# SCH_Mach_DK_Relay_3_Kenh.net
KiCad netlist of a schematic drawn in Altium Designer
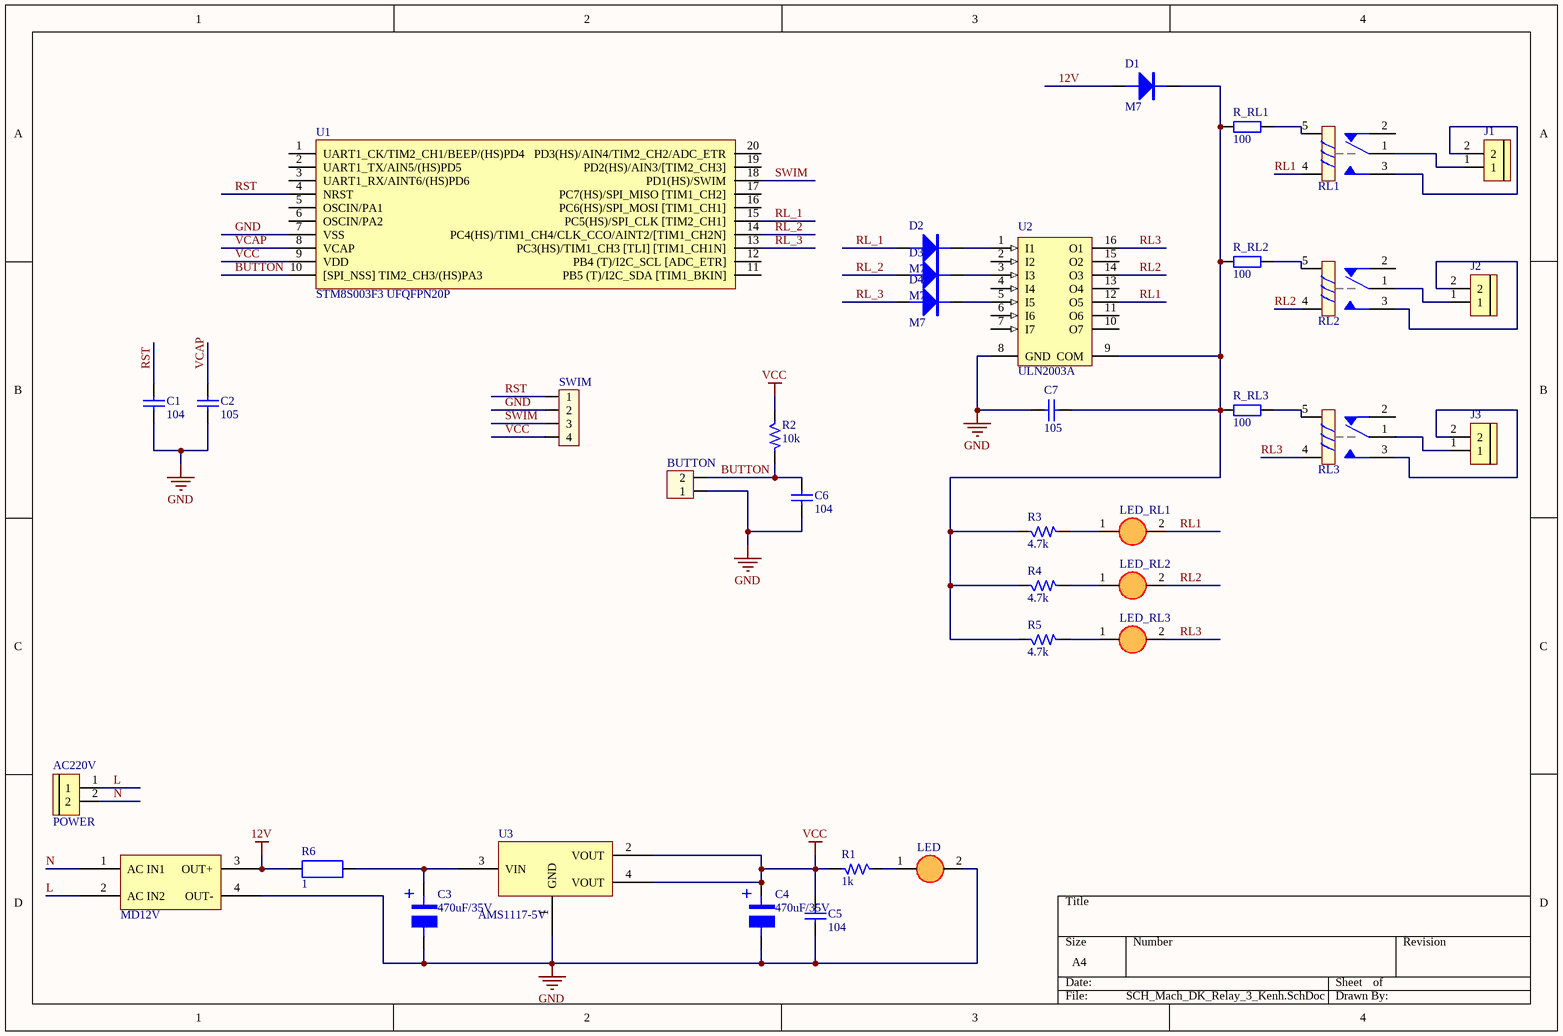
[diagram p0: SCH_Mach_DK_Relay_3_Kenh.SchDoc]

(export (version "E")
  (design (tool "Eeschema 10.0.6"))
  (components
    (comp (ref "AC220V")
      (value "POWER")
      (footprint "BIG_Header 2")
      (description "Big Header 2")
      (libsource (lib "") (part "Header 2_1"))
    )
    (comp (ref "BUTTON")
      (value "Header 2")
      (footprint "Header 2 Duc Cong 2.54")
      (description "Header 2 (Green)")
      (libsource (lib "MH_THU VIEN CHUAN 12-03-2015") (part "Hed2"))
    )
    (comp (ref "C1")
      (value "104")
      (footprint "Tu 0805")
      (libsource (lib "MH_THU VIEN CHUAN 12-03-2015") (part "CAP 0805"))
    )
    (comp (ref "C2")
      (value "105")
      (footprint "Tu 0805")
      (libsource (lib "MH_THU VIEN CHUAN 12-03-2015") (part "CAP 0805"))
    )
    (comp (ref "C3")
      (value "470uF/35V")
      (footprint "MH_THU VIEN CHUAN 13-03-2015 :Tu Hoa 450uF - 16V")
      (libsource (lib "MH_THU VIEN CHUAN 12-03-2015") (part "Cap100uF 50V"))
    )
    (comp (ref "C4")
      (value "470uF/35V")
      (footprint "MH_THU VIEN CHUAN 13-03-2015 :Tu Hoa 450uF - 16V")
      (libsource (lib "MH_THU VIEN CHUAN 12-03-2015") (part "Cap100uF 50V"))
    )
    (comp (ref "C5")
      (value "104")
      (footprint "Tu 0805")
      (libsource (lib "MH_THU VIEN CHUAN 12-03-2015") (part "CAP 0805"))
    )
    (comp (ref "C6")
      (value "104")
      (footprint "Tu 0805")
      (libsource (lib "MH_THU VIEN CHUAN 12-03-2015") (part "CAP 0805"))
    )
    (comp (ref "C7")
      (value "105")
      (footprint "Tu 0805")
      (libsource (lib "MH_THU VIEN CHUAN 12-03-2015") (part "CAP 0805"))
    )
    (comp (ref "D1")
      (value "M7")
      (footprint "SMB")
      (description "Diode")
      (libsource (lib "MH_THU VIEN CHUAN 12-03-2015") (part "DIODE"))
    )
    (comp (ref "D2")
      (value "M7")
      (footprint "SMB")
      (description "Diode")
      (libsource (lib "MH_THU VIEN CHUAN 12-03-2015") (part "DIODE"))
    )
    (comp (ref "D3")
      (value "M7")
      (footprint "SMB")
      (description "Diode")
      (libsource (lib "MH_THU VIEN CHUAN 12-03-2015") (part "DIODE"))
    )
    (comp (ref "D4")
      (value "M7")
      (footprint "SMB")
      (description "Diode")
      (libsource (lib "MH_THU VIEN CHUAN 12-03-2015") (part "DIODE"))
    )
    (comp (ref "J1")
      (value "Header 2")
      (footprint "BIG_Header 2")
      (description "Big Header 2")
      (libsource (lib "MH_THU VIEN CHUAN 12-03-2015") (part "Header 2"))
    )
    (comp (ref "J2")
      (value "Header 2")
      (footprint "BIG_Header 2")
      (description "Big Header 2")
      (libsource (lib "MH_THU VIEN CHUAN 12-03-2015") (part "Header 2"))
    )
    (comp (ref "J3")
      (value "Header 2")
      (footprint "BIG_Header 2")
      (description "Big Header 2")
      (libsource (lib "MH_THU VIEN CHUAN 12-03-2015") (part "Header 2"))
    )
    (comp (ref "LED")
      (value "LED3")
      (footprint "LED RED 5mm")
      (description "LED 3mm")
      (libsource (lib "MH_THU VIEN CHUAN 12-03-2015") (part "LED 3mm"))
    )
    (comp (ref "LED_RL1")
      (value "LED3")
      (footprint "LED RED 5mm")
      (description "LED 3mm")
      (libsource (lib "MH_THU VIEN CHUAN 12-03-2015") (part "LED 3mm"))
    )
    (comp (ref "LED_RL2")
      (value "LED3")
      (footprint "LED RED 5mm")
      (description "LED 3mm")
      (libsource (lib "MH_THU VIEN CHUAN 12-03-2015") (part "LED 3mm"))
    )
    (comp (ref "LED_RL3")
      (value "LED3")
      (footprint "LED RED 5mm")
      (description "LED 3mm")
      (libsource (lib "MH_THU VIEN CHUAN 12-03-2015") (part "LED 3mm"))
    )
    (comp (ref "MD12V")
      (value "Module Driver LED 1x3W")
      (footprint "Module Driver LED")
      (libsource (lib "MH_THU VIEN CHUAN 12-03-2015") (part "Module DK LED 1X3w"))
    )
    (comp (ref "R1")
      (value "1k")
      (footprint "Tro SMD 0805")
      (description "Resistor 1/4W")
      (libsource (lib "MH_THU VIEN CHUAN 12-03-2015") (part "Res"))
    )
    (comp (ref "R2")
      (value "10k")
      (footprint "Tro SMD 0805")
      (description "Resistor 1/4W")
      (libsource (lib "MH_THU VIEN CHUAN 12-03-2015") (part "Res"))
    )
    (comp (ref "R3")
      (value "4.7k")
      (footprint "Tro SMD 0805")
      (description "Resistor 1/4W")
      (libsource (lib "MH_THU VIEN CHUAN 12-03-2015") (part "Res"))
    )
    (comp (ref "R4")
      (value "4.7k")
      (footprint "Tro SMD 0805")
      (description "Resistor 1/4W")
      (libsource (lib "MH_THU VIEN CHUAN 12-03-2015") (part "Res"))
    )
    (comp (ref "R5")
      (value "4.7k")
      (footprint "Tro SMD 0805")
      (description "Resistor 1/4W")
      (libsource (lib "MH_THU VIEN CHUAN 12-03-2015") (part "Res"))
    )
    (comp (ref "R6")
      (value "1")
      (footprint "R2W")
      (description "Resistor 2W")
      (libsource (lib "MH_THU VIEN CHUAN 12-03-2015") (part "R2W"))
    )
    (comp (ref "RL1")
      (value "Relay ?V - 10A")
      (footprint "RELAY5PIN-10A")
      (description "Relay SPDT,10A - 12VDC 5 Pin")
      (libsource (lib "MH_THU VIEN CHUAN 12-03-2015") (part "Relay 10A"))
    )
    (comp (ref "RL2")
      (value "Relay ?V - 10A")
      (footprint "RELAY5PIN-10A")
      (description "Relay SPDT,10A - 12VDC 5 Pin")
      (libsource (lib "MH_THU VIEN CHUAN 12-03-2015") (part "Relay 10A"))
    )
    (comp (ref "RL3")
      (value "Relay ?V - 10A")
      (footprint "RELAY5PIN-10A")
      (description "Relay SPDT,10A - 12VDC 5 Pin")
      (libsource (lib "MH_THU VIEN CHUAN 12-03-2015") (part "Relay 10A"))
    )
    (comp (ref "R_RL1")
      (value "100")
      (footprint "1206 SMD")
      (description "Resistor 1/4W")
      (libsource (lib "MH_THU VIEN CHUAN 12-03-2015") (part "R1/4W"))
    )
    (comp (ref "R_RL2")
      (value "100")
      (footprint "1206 SMD")
      (description "Resistor 1/4W")
      (libsource (lib "MH_THU VIEN CHUAN 12-03-2015") (part "R1/4W"))
    )
    (comp (ref "R_RL3")
      (value "100")
      (footprint "1206 SMD")
      (description "Resistor 1/4W")
      (libsource (lib "MH_THU VIEN CHUAN 12-03-2015") (part "R1/4W"))
    )
    (comp (ref "SWIM")
      (value "JP4")
      (footprint "JP4")
      (libsource (lib "MH_THU VIEN CHUAN 12-03-2015") (part "JP4"))
    )
    (comp (ref "U1")
      (value "STM8S003F3 UFQFPN20P")
      (footprint "TSSOP20")
      (libsource (lib "MH_THU VIEN CHUAN 12-03-2015") (part "STM8S003F3 UFQFPN20P"))
    )
    (comp (ref "U2")
      (value "ULN2003A")
      (footprint "SOP16")
      (description "High-Voltage, High-Current Darlington Array")
      (fields (field (name "PUBLISHER") "Altium Limited"))
      (libsource (lib "MH_THU VIEN CHUAN 12-03-2015") (part "ULN2003A"))
    )
    (comp (ref "U3")
      (value "AMS1117-5V")
      (footprint "SOT223-4N")
      (description "AMS")
      (libsource (lib "MH_THU VIEN CHUAN 12-03-2015") (part "AMS1117"))
    )
  )
  (nets
    (net (code "1") (name "/BUTTON") (class "Default")
      (node (ref "BUTTON") (pin "2") (pinfunction "2_2") (pintype "passive"))
      (node (ref "C6") (pin "2") (pinfunction "2_2") (pintype "passive"))
      (node (ref "R2") (pin "2") (pinfunction "2_2") (pintype "passive"))
      (node (ref "U1") (pin "10") (pinfunction "[SPI_NSS]_TIM2_CH3/(HS)PA3_10") (pintype "passive"))
    )
    (net (code "2") (name "/L") (class "Default")
      (node (ref "AC220V") (pin "1") (pinfunction "1_1") (pintype "passive"))
      (node (ref "MD12V") (pin "2") (pinfunction "AC_IN2_2") (pintype "passive"))
    )
    (net (code "3") (name "/N") (class "Default")
      (node (ref "AC220V") (pin "2") (pinfunction "2_2") (pintype "passive"))
      (node (ref "MD12V") (pin "1") (pinfunction "AC_IN1_1") (pintype "passive"))
    )
    (net (code "4") (name "/RL1") (class "Default")
      (node (ref "LED_RL1") (pin "2") (pinfunction "K_2") (pintype "passive"))
      (node (ref "RL1") (pin "4") (pinfunction "4_4") (pintype "passive"))
      (node (ref "U2") (pin "12") (pinfunction "O5_12") (pintype "open_collector"))
    )
    (net (code "5") (name "/RL2") (class "Default")
      (node (ref "LED_RL2") (pin "2") (pinfunction "K_2") (pintype "passive"))
      (node (ref "RL2") (pin "4") (pinfunction "4_4") (pintype "passive"))
      (node (ref "U2") (pin "14") (pinfunction "O3_14") (pintype "open_collector"))
    )
    (net (code "6") (name "/RL3") (class "Default")
      (node (ref "LED_RL3") (pin "2") (pinfunction "K_2") (pintype "passive"))
      (node (ref "RL3") (pin "4") (pinfunction "4_4") (pintype "passive"))
      (node (ref "U2") (pin "16") (pinfunction "O1_16") (pintype "open_collector"))
    )
    (net (code "7") (name "/RL_1") (class "Default")
      (node (ref "D2") (pin "1") (pinfunction "1_1") (pintype "passive"))
      (node (ref "U1") (pin "15") (pinfunction "PC5(HS)/SPI_CLK_[TIM2_CH1]_15") (pintype "passive"))
    )
    (net (code "8") (name "/RL_2") (class "Default")
      (node (ref "D3") (pin "1") (pinfunction "1_1") (pintype "passive"))
      (node (ref "U1") (pin "14") (pinfunction "PC4(HS)/TIM1_CH4/CLK_CCO/AINT2/[TIM1_CH2N]_14") (pintype "passive"))
    )
    (net (code "9") (name "/RL_3") (class "Default")
      (node (ref "D4") (pin "1") (pinfunction "1_1") (pintype "passive"))
      (node (ref "U1") (pin "13") (pinfunction "PC3(HS)/TIM1_CH3_[TLI]_[TIM1_CH1N]_13") (pintype "passive"))
    )
    (net (code "10") (name "/RST") (class "Default")
      (node (ref "C1") (pin "2") (pinfunction "2_2") (pintype "passive"))
      (node (ref "SWIM") (pin "1") (pinfunction "1_1") (pintype "passive"))
      (node (ref "U1") (pin "4") (pinfunction "NRST_4") (pintype "passive"))
    )
    (net (code "11") (name "/SWIM") (class "Default")
      (node (ref "SWIM") (pin "3") (pinfunction "3_3") (pintype "passive"))
      (node (ref "U1") (pin "18") (pinfunction "PD1(HS)/SWIM_18") (pintype "passive"))
    )
    (net (code "12") (name "/VCAP") (class "Default")
      (node (ref "C2") (pin "2") (pinfunction "2_2") (pintype "passive"))
      (node (ref "U1") (pin "8") (pinfunction "VCAP_8") (pintype "passive"))
    )
    (net (code "13") (name "12V") (class "Default")
      (node (ref "D1") (pin "1") (pinfunction "1_1") (pintype "passive"))
      (node (ref "MD12V") (pin "3") (pinfunction "OUT+_3") (pintype "passive"))
      (node (ref "R6") (pin "1") (pinfunction "1_1") (pintype "passive"))
    )
    (net (code "14") (name "GND") (class "Default")
      (node (ref "BUTTON") (pin "1") (pinfunction "1_1") (pintype "passive"))
      (node (ref "C1") (pin "1") (pinfunction "1_1") (pintype "passive"))
      (node (ref "C2") (pin "1") (pinfunction "1_1") (pintype "passive"))
      (node (ref "C3") (pin "2") (pinfunction "2_2") (pintype "passive"))
      (node (ref "C4") (pin "2") (pinfunction "2_2") (pintype "passive"))
      (node (ref "C5") (pin "1") (pinfunction "1_1") (pintype "passive"))
      (node (ref "C6") (pin "1") (pinfunction "1_1") (pintype "passive"))
      (node (ref "C7") (pin "2") (pinfunction "2_2") (pintype "passive"))
      (node (ref "LED") (pin "2") (pinfunction "K_2") (pintype "passive"))
      (node (ref "MD12V") (pin "4") (pinfunction "OUT-_4") (pintype "passive"))
      (node (ref "SWIM") (pin "2") (pinfunction "2_2") (pintype "passive"))
      (node (ref "U1") (pin "7") (pinfunction "VSS_7") (pintype "passive"))
      (node (ref "U2") (pin "8") (pinfunction "GND_8") (pintype "power_in"))
      (node (ref "U3") (pin "1") (pinfunction "GND_1") (pintype "passive"))
    )
    (net (code "15") (name "Net-(J1-Pad1)") (class "Default")
      (node (ref "J1") (pin "1") (pinfunction "1_1") (pintype "passive"))
      (node (ref "RL1") (pin "1") (pinfunction "1_1") (pintype "passive"))
    )
    (net (code "16") (name "Net-(J1-Pad2)") (class "Default")
      (node (ref "J1") (pin "2") (pinfunction "2_2") (pintype "passive"))
      (node (ref "RL1") (pin "3") (pinfunction "3_3") (pintype "passive"))
    )
    (net (code "17") (name "Net-(J2-Pad1)") (class "Default")
      (node (ref "J2") (pin "1") (pinfunction "1_1") (pintype "passive"))
      (node (ref "RL2") (pin "1") (pinfunction "1_1") (pintype "passive"))
    )
    (net (code "18") (name "Net-(J2-Pad2)") (class "Default")
      (node (ref "J2") (pin "2") (pinfunction "2_2") (pintype "passive"))
      (node (ref "RL2") (pin "3") (pinfunction "3_3") (pintype "passive"))
    )
    (net (code "19") (name "Net-(J3-Pad1)") (class "Default")
      (node (ref "J3") (pin "1") (pinfunction "1_1") (pintype "passive"))
      (node (ref "RL3") (pin "1") (pinfunction "1_1") (pintype "passive"))
    )
    (net (code "20") (name "Net-(J3-Pad2)") (class "Default")
      (node (ref "J3") (pin "2") (pinfunction "2_2") (pintype "passive"))
      (node (ref "RL3") (pin "3") (pinfunction "3_3") (pintype "passive"))
    )
    (net (code "21") (name "Net-(LED-A)") (class "Default")
      (node (ref "LED") (pin "1") (pinfunction "A_1") (pintype "passive"))
      (node (ref "R1") (pin "1") (pinfunction "1_1") (pintype "passive"))
    )
    (net (code "22") (name "Net-(LED_RL1-A)") (class "Default")
      (node (ref "LED_RL1") (pin "1") (pinfunction "A_1") (pintype "passive"))
      (node (ref "R3") (pin "2") (pinfunction "2_2") (pintype "passive"))
    )
    (net (code "23") (name "Net-(LED_RL2-A)") (class "Default")
      (node (ref "LED_RL2") (pin "1") (pinfunction "A_1") (pintype "passive"))
      (node (ref "R4") (pin "2") (pinfunction "2_2") (pintype "passive"))
    )
    (net (code "24") (name "Net-(LED_RL3-A)") (class "Default")
      (node (ref "LED_RL3") (pin "1") (pinfunction "A_1") (pintype "passive"))
      (node (ref "R5") (pin "2") (pinfunction "2_2") (pintype "passive"))
    )
    (net (code "25") (name "Net-(RL1-Pad5)") (class "Default")
      (node (ref "RL1") (pin "5") (pinfunction "5_5") (pintype "passive"))
      (node (ref "R_RL1") (pin "2") (pinfunction "2_2") (pintype "passive"))
    )
    (net (code "26") (name "Net-(RL2-Pad5)") (class "Default")
      (node (ref "RL2") (pin "5") (pinfunction "5_5") (pintype "passive"))
      (node (ref "R_RL2") (pin "2") (pinfunction "2_2") (pintype "passive"))
    )
    (net (code "27") (name "Net-(RL3-Pad5)") (class "Default")
      (node (ref "RL3") (pin "5") (pinfunction "5_5") (pintype "passive"))
      (node (ref "R_RL3") (pin "2") (pinfunction "2_2") (pintype "passive"))
    )
    (net (code "28") (name "Net-(U2-COM)") (class "Default")
      (node (ref "C7") (pin "1") (pinfunction "1_1") (pintype "passive"))
      (node (ref "D1") (pin "2") (pinfunction "2_2") (pintype "passive"))
      (node (ref "R3") (pin "1") (pinfunction "1_1") (pintype "passive"))
      (node (ref "R4") (pin "1") (pinfunction "1_1") (pintype "passive"))
      (node (ref "R5") (pin "1") (pinfunction "1_1") (pintype "passive"))
      (node (ref "R_RL1") (pin "1") (pinfunction "1_1") (pintype "passive"))
      (node (ref "R_RL2") (pin "1") (pinfunction "1_1") (pintype "passive"))
      (node (ref "R_RL3") (pin "1") (pinfunction "1_1") (pintype "passive"))
      (node (ref "U2") (pin "9") (pinfunction "COM_9") (pintype "passive"))
    )
    (net (code "29") (name "Net-(U2-I1)") (class "Default")
      (node (ref "D2") (pin "2") (pinfunction "2_2") (pintype "passive"))
      (node (ref "U2") (pin "1") (pinfunction "I1_1") (pintype "input"))
    )
    (net (code "30") (name "Net-(U2-I3)") (class "Default")
      (node (ref "D3") (pin "2") (pinfunction "2_2") (pintype "passive"))
      (node (ref "U2") (pin "3") (pinfunction "I3_3") (pintype "input"))
    )
    (net (code "31") (name "Net-(U2-I5)") (class "Default")
      (node (ref "D4") (pin "2") (pinfunction "2_2") (pintype "passive"))
      (node (ref "U2") (pin "5") (pinfunction "I5_5") (pintype "input"))
    )
    (net (code "32") (name "Net-(U3-VIN)") (class "Default")
      (node (ref "C3") (pin "1") (pinfunction "1_1") (pintype "passive"))
      (node (ref "R6") (pin "2") (pinfunction "2_2") (pintype "passive"))
      (node (ref "U3") (pin "3") (pinfunction "VIN_3") (pintype "passive"))
    )
    (net (code "33") (name "VCC") (class "Default")
      (node (ref "C4") (pin "1") (pinfunction "1_1") (pintype "passive"))
      (node (ref "C5") (pin "2") (pinfunction "2_2") (pintype "passive"))
      (node (ref "R1") (pin "2") (pinfunction "2_2") (pintype "passive"))
      (node (ref "R2") (pin "1") (pinfunction "1_1") (pintype "passive"))
      (node (ref "SWIM") (pin "4") (pinfunction "4_4") (pintype "passive"))
      (node (ref "U1") (pin "9") (pinfunction "VDD_9") (pintype "passive"))
      (node (ref "U3") (pin "2") (pinfunction "VOUT_2") (pintype "passive"))
      (node (ref "U3") (pin "4") (pinfunction "VOUT_4") (pintype "passive"))
    )
    (net (code "34") (name "unconnected-(RL1-Pad2)") (class "Default")
      (node (ref "RL1") (pin "2") (pinfunction "2_2") (pintype "passive"))
    )
    (net (code "35") (name "unconnected-(RL2-Pad2)") (class "Default")
      (node (ref "RL2") (pin "2") (pinfunction "2_2") (pintype "passive"))
    )
    (net (code "36") (name "unconnected-(RL3-Pad2)") (class "Default")
      (node (ref "RL3") (pin "2") (pinfunction "2_2") (pintype "passive"))
    )
    (net (code "37") (name "unconnected-(U1-OSCIN{slash}PA1-Pad5)") (class "Default")
      (node (ref "U1") (pin "5") (pinfunction "OSCIN/PA1_5") (pintype "passive"))
    )
    (net (code "38") (name "unconnected-(U1-OSCIN{slash}PA2-Pad6)") (class "Default")
      (node (ref "U1") (pin "6") (pinfunction "OSCIN/PA2_6") (pintype "passive"))
    )
    (net (code "39") (name "unconnected-(U1-PB4_(T){slash}I2C_SCL_[ADC_ETR]-Pad12)") (class "Default")
      (node (ref "U1") (pin "12") (pinfunction "PB4_(T)/I2C_SCL_[ADC_ETR]_12") (pintype "passive"))
    )
    (net (code "40") (name "unconnected-(U1-PB5_(T){slash}I2C_SDA_[TIM1_BKIN]-Pad11)") (class "Default")
      (node (ref "U1") (pin "11") (pinfunction "PB5_(T)/I2C_SDA_[TIM1_BKIN]_11") (pintype "passive"))
    )
    (net (code "41") (name "unconnected-(U1-PC6(HS){slash}SPI_MOSI_[TIM1_CH1]-Pad16)") (class "Default")
      (node (ref "U1") (pin "16") (pinfunction "PC6(HS)/SPI_MOSI_[TIM1_CH1]_16") (pintype "passive"))
    )
    (net (code "42") (name "unconnected-(U1-PC7(HS){slash}SPI_MISO_[TIM1_CH2]-Pad17)") (class "Default")
      (node (ref "U1") (pin "17") (pinfunction "PC7(HS)/SPI_MISO_[TIM1_CH2]_17") (pintype "passive"))
    )
    (net (code "43") (name "unconnected-(U1-PD2(HS){slash}AIN3{slash}[TIM2_CH3]-Pad19)") (class "Default")
      (node (ref "U1") (pin "19") (pinfunction "PD2(HS)/AIN3/[TIM2_CH3]_19") (pintype "passive"))
    )
    (net (code "44") (name "unconnected-(U1-PD3(HS){slash}AIN4{slash}TIM2_CH2{slash}ADC_ETR-Pad20)") (class "Default")
      (node (ref "U1") (pin "20") (pinfunction "PD3(HS)/AIN4/TIM2_CH2/ADC_ETR_20") (pintype "passive"))
    )
    (net (code "45") (name "unconnected-(U1-UART1_CK{slash}TIM2_CH1{slash}BEEP{slash}(HS)PD4-Pad1)") (class "Default")
      (node (ref "U1") (pin "1") (pinfunction "UART1_CK/TIM2_CH1/BEEP/(HS)PD4_1") (pintype "passive"))
    )
    (net (code "46") (name "unconnected-(U1-UART1_RX{slash}AINT6{slash}(HS)PD6-Pad3)") (class "Default")
      (node (ref "U1") (pin "3") (pinfunction "UART1_RX/AINT6/(HS)PD6_3") (pintype "passive"))
    )
    (net (code "47") (name "unconnected-(U1-UART1_TX{slash}AIN5{slash}(HS)PD5-Pad2)") (class "Default")
      (node (ref "U1") (pin "2") (pinfunction "UART1_TX/AIN5/(HS)PD5_2") (pintype "passive"))
    )
    (net (code "48") (name "unconnected-(U2-I2-Pad2)") (class "Default")
      (node (ref "U2") (pin "2") (pinfunction "I2_2") (pintype "input"))
    )
    (net (code "49") (name "unconnected-(U2-I4-Pad4)") (class "Default")
      (node (ref "U2") (pin "4") (pinfunction "I4_4") (pintype "input"))
    )
    (net (code "50") (name "unconnected-(U2-I6-Pad6)") (class "Default")
      (node (ref "U2") (pin "6") (pinfunction "I6_6") (pintype "input"))
    )
    (net (code "51") (name "unconnected-(U2-I7-Pad7)") (class "Default")
      (node (ref "U2") (pin "7") (pinfunction "I7_7") (pintype "input"))
    )
    (net (code "52") (name "unconnected-(U2-O2-Pad15)") (class "Default")
      (node (ref "U2") (pin "15") (pinfunction "O2_15") (pintype "open_collector"))
    )
    (net (code "53") (name "unconnected-(U2-O4-Pad13)") (class "Default")
      (node (ref "U2") (pin "13") (pinfunction "O4_13") (pintype "open_collector"))
    )
    (net (code "54") (name "unconnected-(U2-O6-Pad11)") (class "Default")
      (node (ref "U2") (pin "11") (pinfunction "O6_11") (pintype "open_collector"))
    )
    (net (code "55") (name "unconnected-(U2-O7-Pad10)") (class "Default")
      (node (ref "U2") (pin "10") (pinfunction "O7_10") (pintype "open_collector"))
    )
  )
)
